# filterbank_amp.net
KiCad netlist of a schematic drawn in Altium Designer
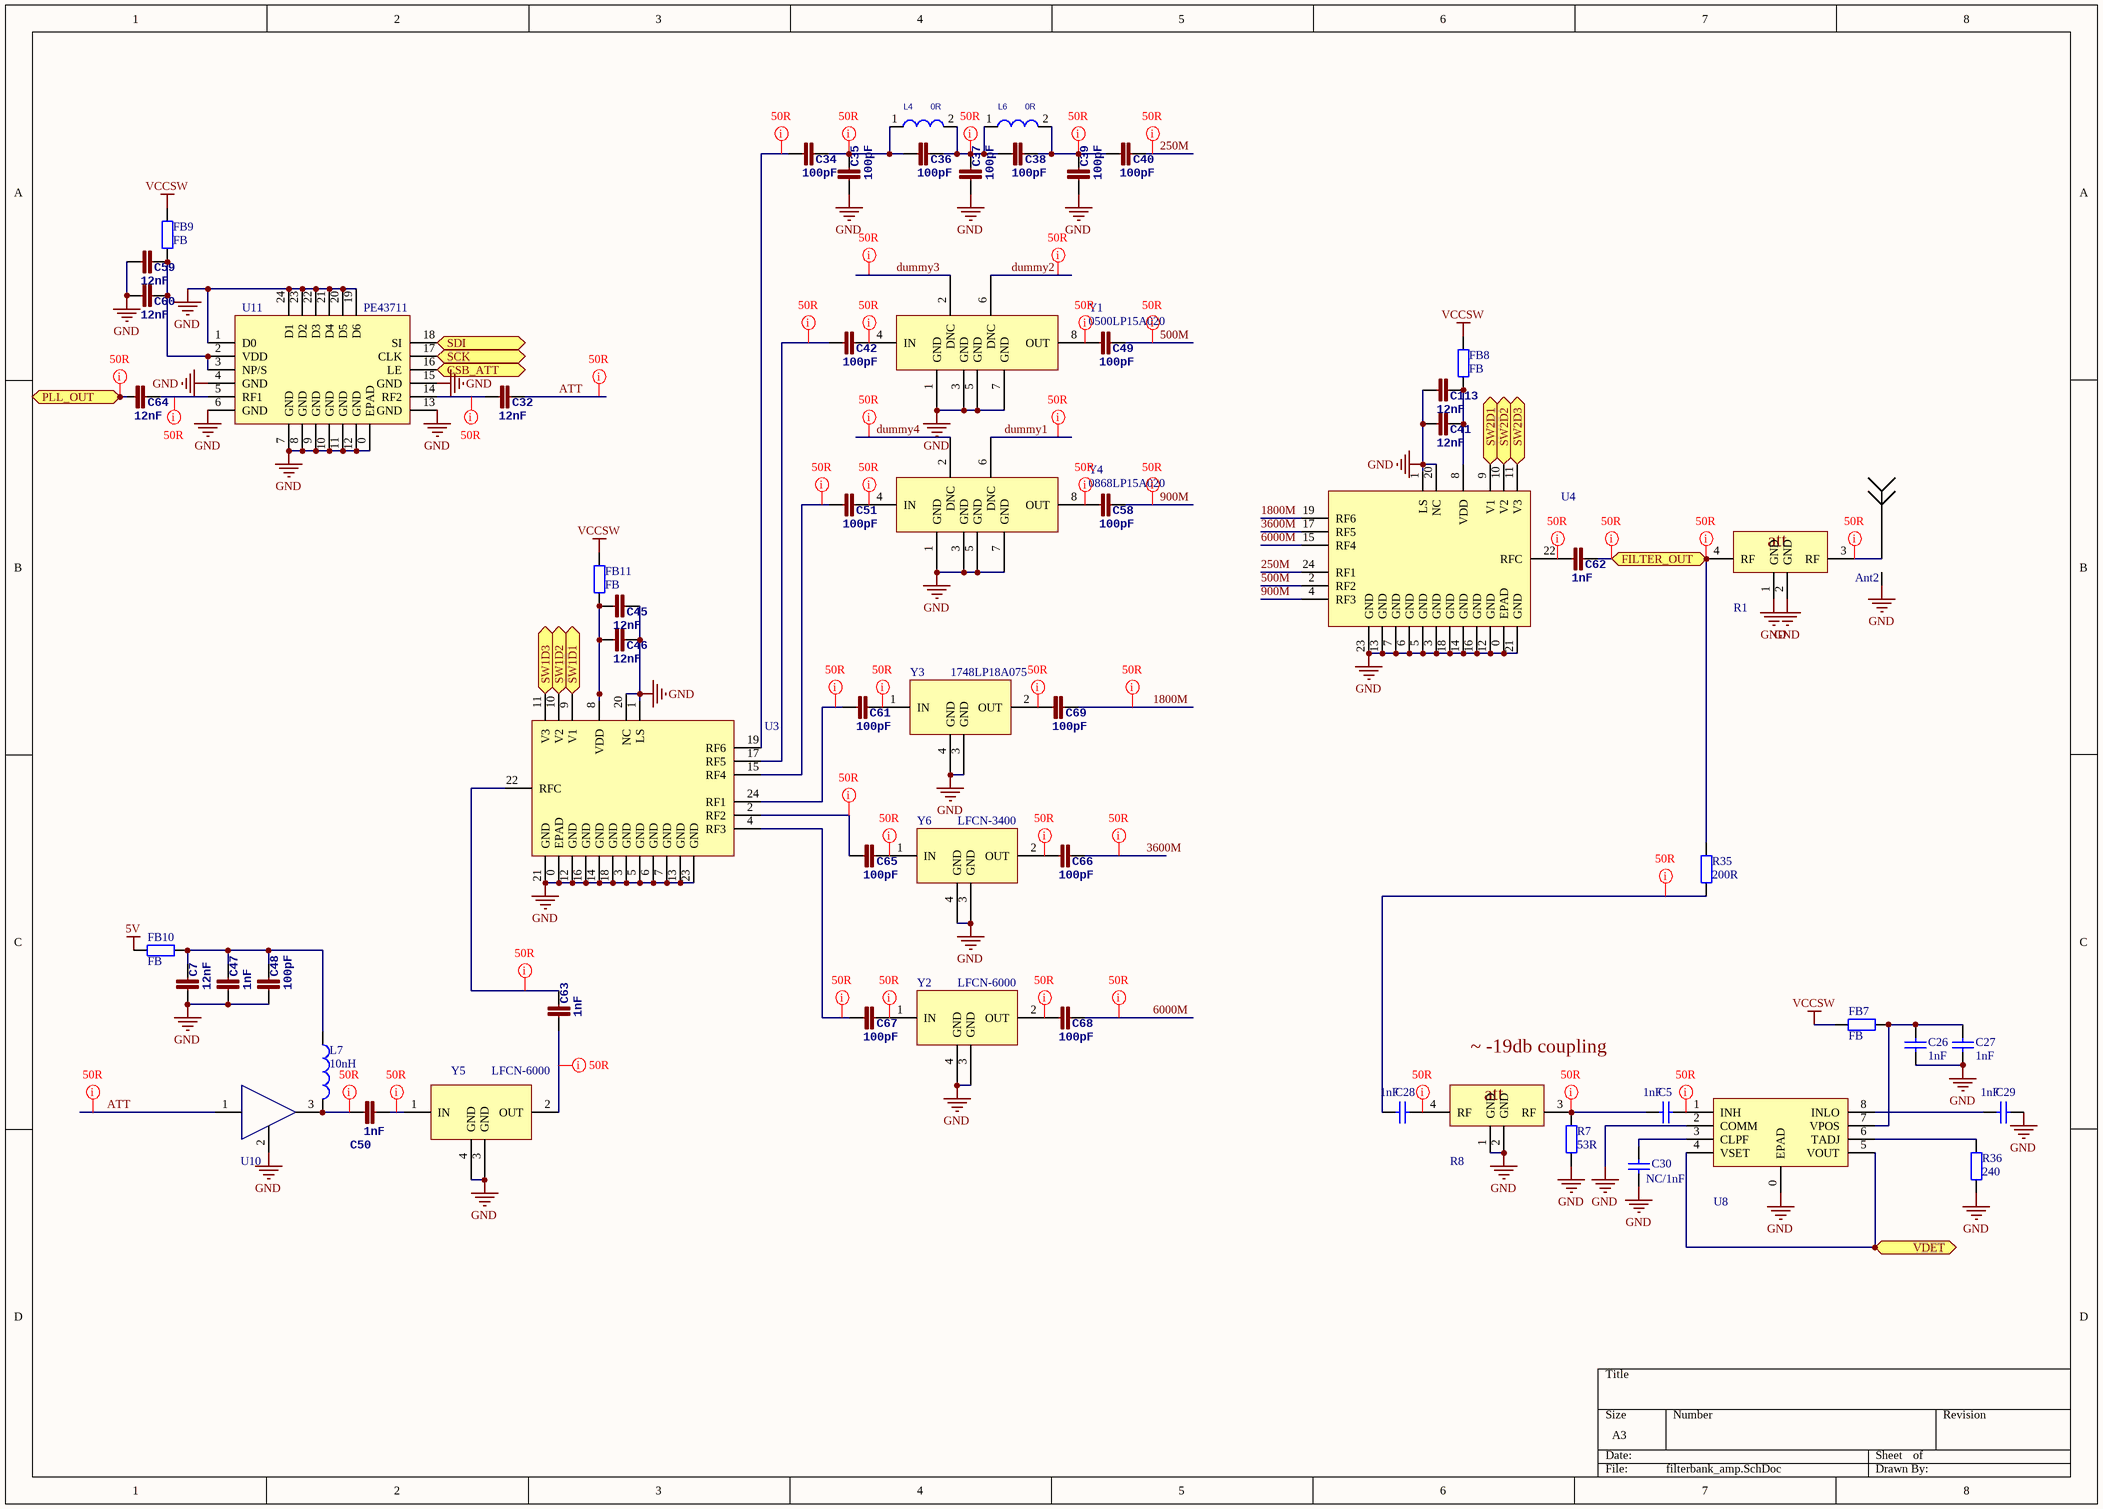
[diagram p0: filterbank_amp.SchDoc]

(export (version "E")
  (design (tool "Eeschema 10.0.6"))
  (components
    (comp (ref "Ant2") (value "Antenna") (footprint "SMA-2") (libsource (lib "F4SDR") (part "Antenna")))
    (comp (ref "C5")
      (value "1nF")
      (footprint "0402")
      (description "Capacitor")
      (fields (field (name "PUBLISHER") "Altium Limited"))
      (libsource (lib "RTC6705") (part "Cap"))
    )
    (comp (ref "C7")
      (value "12nF")
      (footprint "0805")
      (description "<b>Capacitor</b>\nStandard 0603 ceramic capacitor, and 0.1\" leaded capacitor.")
      (fields (field (name "PARTNO") "CC0402ZRY5V7BB104"))
      (libsource (lib "pixhawk2") (part "CAP0402-CAP"))
    )
    (comp (ref "C26")
      (value "1nF")
      (footprint "0402")
      (description "Capacitor")
      (fields (field (name "PUBLISHER") "Altium Limited"))
      (libsource (lib "RTC6705") (part "Cap"))
    )
    (comp (ref "C27")
      (value "1nF")
      (footprint "0402")
      (description "Capacitor")
      (fields (field (name "PUBLISHER") "Altium Limited"))
      (libsource (lib "RTC6705") (part "Cap"))
    )
    (comp (ref "C28")
      (value "1nF")
      (footprint "0402")
      (description "Capacitor")
      (fields (field (name "PUBLISHER") "Altium Limited"))
      (libsource (lib "RTC6705") (part "Cap"))
    )
    (comp (ref "C29")
      (value "1nF")
      (footprint "0402")
      (description "Capacitor")
      (fields (field (name "PUBLISHER") "Altium Limited"))
      (libsource (lib "RTC6705") (part "Cap"))
    )
    (comp (ref "C30")
      (value "NC/1nF")
      (footprint "0402")
      (description "Capacitor")
      (fields (field (name "PUBLISHER") "Altium Limited"))
      (libsource (lib "RTC6705") (part "Cap"))
    )
    (comp (ref "C32")
      (value "12nF")
      (footprint "0402")
      (description "<b>Capacitor</b>\nStandard 0603 ceramic capacitor, and 0.1\" leaded capacitor.")
      (fields (field (name "PARTNO") "CC0402ZRY5V7BB104"))
      (libsource (lib "") (part "CAP0402-CAP_1"))
    )
    (comp (ref "C34")
      (value "100pF")
      (footprint "0402")
      (description "<b>Capacitor</b>\nStandard 0603 ceramic capacitor, and 0.1\" leaded capacitor.")
      (fields (field (name "PARTNO") "CC0402ZRY5V7BB104"))
      (libsource (lib "") (part "CAP0402-CAP_1"))
    )
    (comp (ref "C35")
      (value "100pF")
      (footprint "0402")
      (description "<b>Capacitor</b>\nStandard 0603 ceramic capacitor, and 0.1\" leaded capacitor.")
      (fields (field (name "PARTNO") "CC0402ZRY5V7BB104"))
      (libsource (lib "pixhawk2") (part "CAP0402-CAP"))
    )
    (comp (ref "C36")
      (value "100pF")
      (footprint "0402")
      (description "<b>Capacitor</b>\nStandard 0603 ceramic capacitor, and 0.1\" leaded capacitor.")
      (fields (field (name "PARTNO") "CC0402ZRY5V7BB104"))
      (libsource (lib "") (part "CAP0402-CAP_1"))
    )
    (comp (ref "C37")
      (value "100pF")
      (footprint "0402")
      (description "<b>Capacitor</b>\nStandard 0603 ceramic capacitor, and 0.1\" leaded capacitor.")
      (fields (field (name "PARTNO") "CC0402ZRY5V7BB104"))
      (libsource (lib "pixhawk2") (part "CAP0402-CAP"))
    )
    (comp (ref "C38")
      (value "100pF")
      (footprint "0402")
      (description "<b>Capacitor</b>\nStandard 0603 ceramic capacitor, and 0.1\" leaded capacitor.")
      (fields (field (name "PARTNO") "CC0402ZRY5V7BB104"))
      (libsource (lib "") (part "CAP0402-CAP_1"))
    )
    (comp (ref "C39")
      (value "100pF")
      (footprint "0402")
      (description "<b>Capacitor</b>\nStandard 0603 ceramic capacitor, and 0.1\" leaded capacitor.")
      (fields (field (name "PARTNO") "CC0402ZRY5V7BB104"))
      (libsource (lib "pixhawk2") (part "CAP0402-CAP"))
    )
    (comp (ref "C40")
      (value "100pF")
      (footprint "0402")
      (description "<b>Capacitor</b>\nStandard 0603 ceramic capacitor, and 0.1\" leaded capacitor.")
      (fields (field (name "PARTNO") "CC0402ZRY5V7BB104"))
      (libsource (lib "") (part "CAP0402-CAP_1"))
    )
    (comp (ref "C41")
      (value "12nF")
      (footprint "0402")
      (description "<b>Capacitor</b>\nStandard 0603 ceramic capacitor, and 0.1\" leaded capacitor.")
      (fields (field (name "PARTNO") "CC0402ZRY5V7BB104"))
      (libsource (lib "") (part "CAP0402-CAP_1"))
    )
    (comp (ref "C42")
      (value "100pF")
      (footprint "0402")
      (description "<b>Capacitor</b>\nStandard 0603 ceramic capacitor, and 0.1\" leaded capacitor.")
      (fields (field (name "PARTNO") "CC0402ZRY5V7BB104"))
      (libsource (lib "") (part "CAP0402-CAP_1"))
    )
    (comp (ref "C45")
      (value "12nF")
      (footprint "0402")
      (description "<b>Capacitor</b>\nStandard 0603 ceramic capacitor, and 0.1\" leaded capacitor.")
      (fields (field (name "PARTNO") "CC0402ZRY5V7BB104"))
      (libsource (lib "") (part "CAP0402-CAP_1"))
    )
    (comp (ref "C46")
      (value "12nF")
      (footprint "0402")
      (description "<b>Capacitor</b>\nStandard 0603 ceramic capacitor, and 0.1\" leaded capacitor.")
      (fields (field (name "PARTNO") "CC0402ZRY5V7BB104"))
      (libsource (lib "") (part "CAP0402-CAP_1"))
    )
    (comp (ref "C47")
      (value "1nF")
      (footprint "0402")
      (description "<b>Capacitor</b>\nStandard 0603 ceramic capacitor, and 0.1\" leaded capacitor.")
      (fields (field (name "PARTNO") "CC0402ZRY5V7BB104"))
      (libsource (lib "pixhawk2") (part "CAP0402-CAP"))
    )
    (comp (ref "C48")
      (value "100pF")
      (footprint "0402")
      (description "<b>Capacitor</b>\nStandard 0603 ceramic capacitor, and 0.1\" leaded capacitor.")
      (fields (field (name "PARTNO") "CC0402ZRY5V7BB104"))
      (libsource (lib "pixhawk2") (part "CAP0402-CAP"))
    )
    (comp (ref "C49")
      (value "100pF")
      (footprint "0402")
      (description "<b>Capacitor</b>\nStandard 0603 ceramic capacitor, and 0.1\" leaded capacitor.")
      (fields (field (name "PARTNO") "CC0402ZRY5V7BB104"))
      (libsource (lib "") (part "CAP0402-CAP_1"))
    )
    (comp (ref "C50")
      (value "1nF")
      (footprint "0402")
      (description "<b>Capacitor</b>\nStandard 0603 ceramic capacitor, and 0.1\" leaded capacitor.")
      (fields (field (name "PARTNO") "CC0402ZRY5V7BB104"))
      (libsource (lib "") (part "CAP0402-CAP_1"))
    )
    (comp (ref "C51")
      (value "100pF")
      (footprint "0402")
      (description "<b>Capacitor</b>\nStandard 0603 ceramic capacitor, and 0.1\" leaded capacitor.")
      (fields (field (name "PARTNO") "CC0402ZRY5V7BB104"))
      (libsource (lib "") (part "CAP0402-CAP_1"))
    )
    (comp (ref "C58")
      (value "100pF")
      (footprint "0402")
      (description "<b>Capacitor</b>\nStandard 0603 ceramic capacitor, and 0.1\" leaded capacitor.")
      (fields (field (name "PARTNO") "CC0402ZRY5V7BB104"))
      (libsource (lib "") (part "CAP0402-CAP_1"))
    )
    (comp (ref "C59")
      (value "12nF")
      (footprint "0402")
      (description "<b>Capacitor</b>\nStandard 0603 ceramic capacitor, and 0.1\" leaded capacitor.")
      (fields (field (name "PARTNO") "CC0402ZRY5V7BB104"))
      (libsource (lib "") (part "CAP0402-CAP_1"))
    )
    (comp (ref "C60")
      (value "12nF")
      (footprint "0402")
      (description "<b>Capacitor</b>\nStandard 0603 ceramic capacitor, and 0.1\" leaded capacitor.")
      (fields (field (name "PARTNO") "CC0402ZRY5V7BB104"))
      (libsource (lib "") (part "CAP0402-CAP_1"))
    )
    (comp (ref "C61")
      (value "100pF")
      (footprint "0402")
      (description "<b>Capacitor</b>\nStandard 0603 ceramic capacitor, and 0.1\" leaded capacitor.")
      (fields (field (name "PARTNO") "CC0402ZRY5V7BB104"))
      (libsource (lib "") (part "CAP0402-CAP_1"))
    )
    (comp (ref "C62")
      (value "1nF")
      (footprint "0402")
      (description "<b>Capacitor</b>\nStandard 0603 ceramic capacitor, and 0.1\" leaded capacitor.")
      (fields (field (name "PARTNO") "CC0402ZRY5V7BB104"))
      (libsource (lib "") (part "CAP0402-CAP_1"))
    )
    (comp (ref "C63")
      (value "1nF")
      (footprint "0402")
      (description "<b>Capacitor</b>\nStandard 0603 ceramic capacitor, and 0.1\" leaded capacitor.")
      (fields (field (name "PARTNO") "CC0402ZRY5V7BB104"))
      (libsource (lib "pixhawk2") (part "CAP0402-CAP"))
    )
    (comp (ref "C64")
      (value "12nF")
      (footprint "0402")
      (description "<b>Capacitor</b>\nStandard 0603 ceramic capacitor, and 0.1\" leaded capacitor.")
      (fields (field (name "PARTNO") "CC0402ZRY5V7BB104"))
      (libsource (lib "") (part "CAP0402-CAP_1"))
    )
    (comp (ref "C65")
      (value "100pF")
      (footprint "0402")
      (description "<b>Capacitor</b>\nStandard 0603 ceramic capacitor, and 0.1\" leaded capacitor.")
      (fields (field (name "PARTNO") "CC0402ZRY5V7BB104"))
      (libsource (lib "") (part "CAP0402-CAP_1"))
    )
    (comp (ref "C66")
      (value "100pF")
      (footprint "0402")
      (description "<b>Capacitor</b>\nStandard 0603 ceramic capacitor, and 0.1\" leaded capacitor.")
      (fields (field (name "PARTNO") "CC0402ZRY5V7BB104"))
      (libsource (lib "") (part "CAP0402-CAP_1"))
    )
    (comp (ref "C67")
      (value "100pF")
      (footprint "0402")
      (description "<b>Capacitor</b>\nStandard 0603 ceramic capacitor, and 0.1\" leaded capacitor.")
      (fields (field (name "PARTNO") "CC0402ZRY5V7BB104"))
      (libsource (lib "") (part "CAP0402-CAP_1"))
    )
    (comp (ref "C68")
      (value "100pF")
      (footprint "0402")
      (description "<b>Capacitor</b>\nStandard 0603 ceramic capacitor, and 0.1\" leaded capacitor.")
      (fields (field (name "PARTNO") "CC0402ZRY5V7BB104"))
      (libsource (lib "") (part "CAP0402-CAP_1"))
    )
    (comp (ref "C69")
      (value "100pF")
      (footprint "0402")
      (description "<b>Capacitor</b>\nStandard 0603 ceramic capacitor, and 0.1\" leaded capacitor.")
      (fields (field (name "PARTNO") "CC0402ZRY5V7BB104"))
      (libsource (lib "") (part "CAP0402-CAP_1"))
    )
    (comp (ref "C113")
      (value "12nF")
      (footprint "0402")
      (description "<b>Capacitor</b>\nStandard 0603 ceramic capacitor, and 0.1\" leaded capacitor.")
      (fields (field (name "PARTNO") "CC0402ZRY5V7BB104"))
      (libsource (lib "") (part "CAP0402-CAP_1"))
    )
    (comp (ref "FB7")
      (value "FB")
      (footprint "0402")
      (description "Resistor")
      (fields (field (name "PUBLISHER") "Altium Limited"))
      (libsource (lib "Miscellaneous Devices") (part "Res2"))
    )
    (comp (ref "FB8")
      (value "FB")
      (footprint "0402")
      (description "Resistor")
      (fields (field (name "PUBLISHER") "Altium Limited"))
      (libsource (lib "") (part "Res2_1"))
    )
    (comp (ref "FB9")
      (value "FB")
      (footprint "0402")
      (description "Resistor")
      (fields (field (name "PUBLISHER") "Altium Limited"))
      (libsource (lib "") (part "Res2_1"))
    )
    (comp (ref "FB10")
      (value "FB")
      (footprint "0402")
      (description "Resistor")
      (fields (field (name "PUBLISHER") "Altium Limited"))
      (libsource (lib "Miscellaneous Devices") (part "Res2"))
    )
    (comp (ref "FB11")
      (value "FB")
      (footprint "0402")
      (description "Resistor")
      (fields (field (name "PUBLISHER") "Altium Limited"))
      (libsource (lib "") (part "Res2_1"))
    )
    (comp (ref "L4") (value "0R") (footprint "0402") (libsource (lib "*") (part "L/2.5*2.0")))
    (comp (ref "L6") (value "0R") (footprint "0402") (libsource (lib "*") (part "L/2.5*2.0")))
    (comp (ref "L7")
      (value "10nH")
      (footprint "0402")
      (description "Inductor")
      (fields (field (name "PUBLISHER") "Altium Limited"))
      (libsource (lib "Miscellaneous Devices") (part "Inductor"))
    )
    (comp (ref "R1")
      (value "EXB24-RF-ATT")
      (footprint "EXB24AT-RF-ATT")
      (libsource (lib "F4SDR") (part "EXB24-RF-ATT"))
    )
    (comp (ref "R7")
      (value "53R")
      (footprint "0402")
      (description "Resistor")
      (fields (field (name "PUBLISHER") "Altium Limited"))
      (libsource (lib "") (part "Res2_2"))
    )
    (comp (ref "R8")
      (value "EXB24-RF-ATT")
      (footprint "EXB24AT-RF-ATT")
      (libsource (lib "F4SDR") (part "EXB24-RF-ATT"))
    )
    (comp (ref "R35")
      (value "200R")
      (footprint "0402")
      (description "Resistor")
      (fields (field (name "PUBLISHER") "Altium Limited"))
      (libsource (lib "") (part "Res2_2"))
    )
    (comp (ref "R36")
      (value "240")
      (footprint "0402")
      (description "Resistor")
      (fields (field (name "PUBLISHER") "Altium Limited"))
      (libsource (lib "") (part "Res2_2"))
    )
    (comp (ref "U3") (value "PE42462") (footprint "PE42462") (libsource (lib "F4SDR") (part "PE42462")))
    (comp (ref "U4") (value "PE42462") (footprint "PE42462") (libsource (lib "") (part "PE42462_1")))
    (comp (ref "U8") (value "AD8319") (footprint "AD8319") (libsource (lib "F4SDR") (part "AD8319")))
    (comp (ref "U10") (value "AMP-SOT89") (footprint "SOT-89") (libsource (lib "F4SDR") (part "AMP-SOT89")))
    (comp (ref "U11") (value "PE43711") (footprint "PE43711") (libsource (lib "F4SDR") (part "PE43711")))
    (comp (ref "Y1")
      (value "0500LP15A020")
      (footprint "5515LP15A730/0868LP15A020")
      (libsource (lib "F4SDR") (part "5515LP15A730/0868LP15A020"))
    )
    (comp (ref "Y2")
      (value "LFCN-6000")
      (footprint "1748LP18A075")
      (libsource (lib "F4SDR") (part "1748LP18A075"))
    )
    (comp (ref "Y3")
      (value "1748LP18A075")
      (footprint "1748LP18A075")
      (libsource (lib "F4SDR") (part "1748LP18A075"))
    )
    (comp (ref "Y4")
      (value "0868LP15A020")
      (footprint "5515LP15A730/0868LP15A020")
      (libsource (lib "F4SDR") (part "5515LP15A730/0868LP15A020"))
    )
    (comp (ref "Y5")
      (value "LFCN-6000")
      (footprint "1748LP18A075")
      (libsource (lib "F4SDR") (part "1748LP18A075"))
    )
    (comp (ref "Y6")
      (value "LFCN-3400")
      (footprint "1748LP18A075")
      (libsource (lib "F4SDR") (part "1748LP18A075"))
    )
  )
  (nets
    (net (code "1") (name "/250M") (class "Default")
      (node (ref "C40") (pin "2") (pinfunction "2_2") (pintype "passive"))
      (node (ref "U4") (pin "24") (pinfunction "RF1_24") (pintype "passive"))
    )
    (net (code "2") (name "/500M") (class "Default")
      (node (ref "C49") (pin "2") (pinfunction "2_2") (pintype "passive"))
      (node (ref "U4") (pin "2") (pinfunction "RF2_2") (pintype "passive"))
    )
    (net (code "3") (name "/900M") (class "Default")
      (node (ref "C58") (pin "2") (pinfunction "2_2") (pintype "passive"))
      (node (ref "U4") (pin "4") (pinfunction "RF3_4") (pintype "passive"))
    )
    (net (code "4") (name "/1800M") (class "Default")
      (node (ref "C69") (pin "2") (pinfunction "2_2") (pintype "passive"))
      (node (ref "U4") (pin "19") (pinfunction "RF6_19") (pintype "passive"))
    )
    (net (code "5") (name "/3600M") (class "Default")
      (node (ref "C66") (pin "2") (pinfunction "2_2") (pintype "passive"))
      (node (ref "U4") (pin "17") (pinfunction "RF5_17") (pintype "passive"))
    )
    (net (code "6") (name "/6000M") (class "Default")
      (node (ref "C68") (pin "2") (pinfunction "2_2") (pintype "passive"))
      (node (ref "U4") (pin "15") (pinfunction "RF4_15") (pintype "passive"))
    )
    (net (code "7") (name "/ATT") (class "Default")
      (node (ref "C32") (pin "2") (pinfunction "2_2") (pintype "passive"))
      (node (ref "U10") (pin "1") (pinfunction "1_1") (pintype "passive"))
    )
    (net (code "8") (name "/CSB_ATT") (class "Default")
      (node (ref "U11") (pin "16") (pinfunction "LE_16") (pintype "passive"))
    )
    (net (code "9") (name "/FILTER_OUT") (class "Default")
      (node (ref "C62") (pin "2") (pinfunction "2_2") (pintype "passive"))
      (node (ref "R1") (pin "4") (pinfunction "RF_4") (pintype "passive"))
      (node (ref "R35") (pin "1") (pinfunction "1_1") (pintype "passive"))
    )
    (net (code "10") (name "/PLL_OUT") (class "Default")
      (node (ref "C64") (pin "1") (pinfunction "1_1") (pintype "passive"))
    )
    (net (code "11") (name "/SCK") (class "Default")
      (node (ref "U11") (pin "17") (pinfunction "CLK_17") (pintype "passive"))
    )
    (net (code "12") (name "/SDI") (class "Default")
      (node (ref "U11") (pin "18") (pinfunction "SI_18") (pintype "passive"))
    )
    (net (code "13") (name "/SW1D1") (class "Default")
      (node (ref "U3") (pin "9") (pinfunction "V1_9") (pintype "passive"))
    )
    (net (code "14") (name "/SW1D2") (class "Default")
      (node (ref "U3") (pin "10") (pinfunction "V2_10") (pintype "passive"))
    )
    (net (code "15") (name "/SW1D3") (class "Default")
      (node (ref "U3") (pin "11") (pinfunction "V3_11") (pintype "passive"))
    )
    (net (code "16") (name "/SW2D1") (class "Default")
      (node (ref "U4") (pin "9") (pinfunction "V1_9") (pintype "passive"))
    )
    (net (code "17") (name "/SW2D2") (class "Default")
      (node (ref "U4") (pin "10") (pinfunction "V2_10") (pintype "passive"))
    )
    (net (code "18") (name "/SW2D3") (class "Default")
      (node (ref "U4") (pin "11") (pinfunction "V3_11") (pintype "passive"))
    )
    (net (code "19") (name "/VDET") (class "Default")
      (node (ref "U8") (pin "4") (pinfunction "VSET_4") (pintype "passive"))
      (node (ref "U8") (pin "5") (pinfunction "VOUT_5") (pintype "passive"))
    )
    (net (code "20") (name "/dummy1") (class "Default")
      (node (ref "Y4") (pin "6") (pinfunction "DNC_6") (pintype "passive"))
    )
    (net (code "21") (name "/dummy2") (class "Default")
      (node (ref "Y1") (pin "6") (pinfunction "DNC_6") (pintype "passive"))
    )
    (net (code "22") (name "/dummy3") (class "Default")
      (node (ref "Y1") (pin "2") (pinfunction "DNC_2") (pintype "passive"))
    )
    (net (code "23") (name "/dummy4") (class "Default")
      (node (ref "Y4") (pin "2") (pinfunction "DNC_2") (pintype "passive"))
    )
    (net (code "24") (name "5V") (class "Default")
      (node (ref "FB10") (pin "1") (pinfunction "1_1") (pintype "passive"))
    )
    (net (code "25") (name "GND") (class "Default")
      (node (ref "Ant2") (pin "GND") (pinfunction "G_GND") (pintype "passive"))
      (node (ref "C113") (pin "1") (pinfunction "1_1") (pintype "passive"))
      (node (ref "C26") (pin "1") (pinfunction "1_1") (pintype "passive"))
      (node (ref "C27") (pin "1") (pinfunction "1_1") (pintype "passive"))
      (node (ref "C29") (pin "2") (pinfunction "2_2") (pintype "passive"))
      (node (ref "C30") (pin "1") (pinfunction "1_1") (pintype "passive"))
      (node (ref "C35") (pin "1") (pinfunction "1_1") (pintype "passive"))
      (node (ref "C37") (pin "1") (pinfunction "1_1") (pintype "passive"))
      (node (ref "C39") (pin "1") (pinfunction "1_1") (pintype "passive"))
      (node (ref "C41") (pin "1") (pinfunction "1_1") (pintype "passive"))
      (node (ref "C45") (pin "2") (pinfunction "2_2") (pintype "passive"))
      (node (ref "C46") (pin "2") (pinfunction "2_2") (pintype "passive"))
      (node (ref "C47") (pin "1") (pinfunction "1_1") (pintype "passive"))
      (node (ref "C48") (pin "1") (pinfunction "1_1") (pintype "passive"))
      (node (ref "C59") (pin "1") (pinfunction "1_1") (pintype "passive"))
      (node (ref "C60") (pin "1") (pinfunction "1_1") (pintype "passive"))
      (node (ref "C7") (pin "1") (pinfunction "1_1") (pintype "passive"))
      (node (ref "R1") (pin "1") (pinfunction "GND_1") (pintype "passive"))
      (node (ref "R1") (pin "2") (pinfunction "GND_2") (pintype "passive"))
      (node (ref "R36") (pin "2") (pinfunction "2_2") (pintype "passive"))
      (node (ref "R7") (pin "2") (pinfunction "2_2") (pintype "passive"))
      (node (ref "R8") (pin "1") (pinfunction "GND_1") (pintype "passive"))
      (node (ref "R8") (pin "2") (pinfunction "GND_2") (pintype "passive"))
      (node (ref "U10") (pin "2") (pinfunction "2_2") (pintype "passive"))
      (node (ref "U11") (pin "0") (pinfunction "EPAD_0") (pintype "passive"))
      (node (ref "U11") (pin "1") (pinfunction "D0_1") (pintype "passive"))
      (node (ref "U11") (pin "10") (pinfunction "GND_10") (pintype "passive"))
      (node (ref "U11") (pin "11") (pinfunction "GND_11") (pintype "passive"))
      (node (ref "U11") (pin "12") (pinfunction "GND_12") (pintype "passive"))
      (node (ref "U11") (pin "13") (pinfunction "GND_13") (pintype "passive"))
      (node (ref "U11") (pin "15") (pinfunction "GND_15") (pintype "passive"))
      (node (ref "U11") (pin "19") (pinfunction "D6_19") (pintype "passive"))
      (node (ref "U11") (pin "20") (pinfunction "D5_20") (pintype "passive"))
      (node (ref "U11") (pin "21") (pinfunction "D4_21") (pintype "passive"))
      (node (ref "U11") (pin "22") (pinfunction "D3_22") (pintype "passive"))
      (node (ref "U11") (pin "23") (pinfunction "D2_23") (pintype "passive"))
      (node (ref "U11") (pin "24") (pinfunction "D1_24") (pintype "passive"))
      (node (ref "U11") (pin "4") (pinfunction "GND_4") (pintype "passive"))
      (node (ref "U11") (pin "6") (pinfunction "GND_6") (pintype "passive"))
      (node (ref "U11") (pin "7") (pinfunction "GND_7") (pintype "passive"))
      (node (ref "U11") (pin "8") (pinfunction "GND_8") (pintype "passive"))
      (node (ref "U11") (pin "9") (pinfunction "GND_9") (pintype "passive"))
      (node (ref "U3") (pin "0") (pinfunction "EPAD_0") (pintype "passive"))
      (node (ref "U3") (pin "1") (pinfunction "LS_1") (pintype "passive"))
      (node (ref "U3") (pin "12") (pinfunction "GND_12") (pintype "passive"))
      (node (ref "U3") (pin "13") (pinfunction "GND_13") (pintype "passive"))
      (node (ref "U3") (pin "14") (pinfunction "GND_14") (pintype "passive"))
      (node (ref "U3") (pin "16") (pinfunction "GND_16") (pintype "passive"))
      (node (ref "U3") (pin "18") (pinfunction "GND_18") (pintype "passive"))
      (node (ref "U3") (pin "20") (pinfunction "NC_20") (pintype "passive"))
      (node (ref "U3") (pin "21") (pinfunction "GND_21") (pintype "passive"))
      (node (ref "U3") (pin "23") (pinfunction "GND_23") (pintype "passive"))
      (node (ref "U3") (pin "3") (pinfunction "GND_3") (pintype "passive"))
      (node (ref "U3") (pin "5") (pinfunction "GND_5") (pintype "passive"))
      (node (ref "U3") (pin "6") (pinfunction "GND_6") (pintype "passive"))
      (node (ref "U3") (pin "7") (pinfunction "GND_7") (pintype "passive"))
      (node (ref "U4") (pin "0") (pinfunction "EPAD_0") (pintype "passive"))
      (node (ref "U4") (pin "1") (pinfunction "LS_1") (pintype "passive"))
      (node (ref "U4") (pin "12") (pinfunction "GND_12") (pintype "passive"))
      (node (ref "U4") (pin "13") (pinfunction "GND_13") (pintype "passive"))
      (node (ref "U4") (pin "14") (pinfunction "GND_14") (pintype "passive"))
      (node (ref "U4") (pin "16") (pinfunction "GND_16") (pintype "passive"))
      (node (ref "U4") (pin "18") (pinfunction "GND_18") (pintype "passive"))
      (node (ref "U4") (pin "20") (pinfunction "NC_20") (pintype "passive"))
      (node (ref "U4") (pin "21") (pinfunction "GND_21") (pintype "passive"))
      (node (ref "U4") (pin "23") (pinfunction "GND_23") (pintype "passive"))
      (node (ref "U4") (pin "3") (pinfunction "GND_3") (pintype "passive"))
      (node (ref "U4") (pin "5") (pinfunction "GND_5") (pintype "passive"))
      (node (ref "U4") (pin "6") (pinfunction "GND_6") (pintype "passive"))
      (node (ref "U4") (pin "7") (pinfunction "GND_7") (pintype "passive"))
      (node (ref "U8") (pin "0") (pinfunction "EPAD_0") (pintype "passive"))
      (node (ref "U8") (pin "2") (pinfunction "COMM_2") (pintype "passive"))
      (node (ref "Y1") (pin "1") (pinfunction "GND_1") (pintype "passive"))
      (node (ref "Y1") (pin "3") (pinfunction "GND_3") (pintype "passive"))
      (node (ref "Y1") (pin "5") (pinfunction "GND_5") (pintype "passive"))
      (node (ref "Y1") (pin "7") (pinfunction "GND_7") (pintype "passive"))
      (node (ref "Y2") (pin "3") (pinfunction "GND_3") (pintype "passive"))
      (node (ref "Y2") (pin "4") (pinfunction "GND_4") (pintype "passive"))
      (node (ref "Y3") (pin "3") (pinfunction "GND_3") (pintype "passive"))
      (node (ref "Y3") (pin "4") (pinfunction "GND_4") (pintype "passive"))
      (node (ref "Y4") (pin "1") (pinfunction "GND_1") (pintype "passive"))
      (node (ref "Y4") (pin "3") (pinfunction "GND_3") (pintype "passive"))
      (node (ref "Y4") (pin "5") (pinfunction "GND_5") (pintype "passive"))
      (node (ref "Y4") (pin "7") (pinfunction "GND_7") (pintype "passive"))
      (node (ref "Y5") (pin "3") (pinfunction "GND_3") (pintype "passive"))
      (node (ref "Y5") (pin "4") (pinfunction "GND_4") (pintype "passive"))
      (node (ref "Y6") (pin "3") (pinfunction "GND_3") (pintype "passive"))
      (node (ref "Y6") (pin "4") (pinfunction "GND_4") (pintype "passive"))
    )
    (net (code "26") (name "Net-(Ant2-Pad1)") (class "Default")
      (node (ref "Ant2") (pin "1") (pinfunction "1_1") (pintype "passive"))
      (node (ref "R1") (pin "3") (pinfunction "RF_3") (pintype "passive"))
    )
    (net (code "27") (name "Net-(C5-Pad1)") (class "Default")
      (node (ref "C5") (pin "1") (pinfunction "1_1") (pintype "passive"))
      (node (ref "R7") (pin "1") (pinfunction "1_1") (pintype "passive"))
      (node (ref "R8") (pin "3") (pinfunction "RF_3") (pintype "passive"))
    )
    (net (code "28") (name "Net-(C28-Pad1)") (class "Default")
      (node (ref "C28") (pin "1") (pinfunction "1_1") (pintype "passive"))
      (node (ref "R35") (pin "2") (pinfunction "2_2") (pintype "passive"))
    )
    (net (code "29") (name "Net-(C28-Pad2)") (class "Default")
      (node (ref "C28") (pin "2") (pinfunction "2_2") (pintype "passive"))
      (node (ref "R8") (pin "4") (pinfunction "RF_4") (pintype "passive"))
    )
    (net (code "30") (name "Net-(C34-Pad2)") (class "Default")
      (node (ref "C34") (pin "2") (pinfunction "2_2") (pintype "passive"))
      (node (ref "C35") (pin "2") (pinfunction "2_2") (pintype "passive"))
      (node (ref "C36") (pin "1") (pinfunction "1_1") (pintype "passive"))
      (node (ref "L4") (pin "1") (pinfunction "1_1") (pintype "passive"))
    )
    (net (code "31") (name "Net-(C36-Pad2)") (class "Default")
      (node (ref "C36") (pin "2") (pinfunction "2_2") (pintype "passive"))
      (node (ref "C37") (pin "2") (pinfunction "2_2") (pintype "passive"))
      (node (ref "C38") (pin "1") (pinfunction "1_1") (pintype "passive"))
      (node (ref "L4") (pin "2") (pinfunction "2_2") (pintype "passive"))
      (node (ref "L6") (pin "1") (pinfunction "1_1") (pintype "passive"))
    )
    (net (code "32") (name "Net-(C38-Pad2)") (class "Default")
      (node (ref "C38") (pin "2") (pinfunction "2_2") (pintype "passive"))
      (node (ref "C39") (pin "2") (pinfunction "2_2") (pintype "passive"))
      (node (ref "C40") (pin "1") (pinfunction "1_1") (pintype "passive"))
      (node (ref "L6") (pin "2") (pinfunction "2_2") (pintype "passive"))
    )
    (net (code "33") (name "Net-(C47-Pad2)") (class "Default")
      (node (ref "C47") (pin "2") (pinfunction "2_2") (pintype "passive"))
      (node (ref "C48") (pin "2") (pinfunction "2_2") (pintype "passive"))
      (node (ref "C7") (pin "2") (pinfunction "2_2") (pintype "passive"))
      (node (ref "FB10") (pin "2") (pinfunction "2_2") (pintype "passive"))
      (node (ref "L7") (pin "1") (pinfunction "1_1") (pintype "passive"))
    )
    (net (code "34") (name "Net-(C50-Pad1)") (class "Default")
      (node (ref "C50") (pin "1") (pinfunction "1_1") (pintype "passive"))
      (node (ref "L7") (pin "2") (pinfunction "2_2") (pintype "passive"))
      (node (ref "U10") (pin "3") (pinfunction "3_3") (pintype "passive"))
    )
    (net (code "35") (name "Net-(U3-RF1)") (class "Default")
      (node (ref "C61") (pin "1") (pinfunction "1_1") (pintype "passive"))
      (node (ref "U3") (pin "24") (pinfunction "RF1_24") (pintype "passive"))
    )
    (net (code "36") (name "Net-(U3-RF2)") (class "Default")
      (node (ref "C65") (pin "1") (pinfunction "1_1") (pintype "passive"))
      (node (ref "U3") (pin "2") (pinfunction "RF2_2") (pintype "passive"))
    )
    (net (code "37") (name "Net-(U3-RF3)") (class "Default")
      (node (ref "C67") (pin "1") (pinfunction "1_1") (pintype "passive"))
      (node (ref "U3") (pin "4") (pinfunction "RF3_4") (pintype "passive"))
    )
    (net (code "38") (name "Net-(U3-RF4)") (class "Default")
      (node (ref "C51") (pin "1") (pinfunction "1_1") (pintype "passive"))
      (node (ref "U3") (pin "15") (pinfunction "RF4_15") (pintype "passive"))
    )
    (net (code "39") (name "Net-(U3-RF5)") (class "Default")
      (node (ref "C42") (pin "1") (pinfunction "1_1") (pintype "passive"))
      (node (ref "U3") (pin "17") (pinfunction "RF5_17") (pintype "passive"))
    )
    (net (code "40") (name "Net-(U3-RF6)") (class "Default")
      (node (ref "C34") (pin "1") (pinfunction "1_1") (pintype "passive"))
      (node (ref "U3") (pin "19") (pinfunction "RF6_19") (pintype "passive"))
    )
    (net (code "41") (name "Net-(U3-RFC)") (class "Default")
      (node (ref "C63") (pin "2") (pinfunction "2_2") (pintype "passive"))
      (node (ref "U3") (pin "22") (pinfunction "RFC_22") (pintype "passive"))
    )
    (net (code "42") (name "Net-(U3-VDD)") (class "Default")
      (node (ref "C45") (pin "1") (pinfunction "1_1") (pintype "passive"))
      (node (ref "C46") (pin "1") (pinfunction "1_1") (pintype "passive"))
      (node (ref "FB11") (pin "1") (pinfunction "1_1") (pintype "passive"))
      (node (ref "U3") (pin "8") (pinfunction "VDD_8") (pintype "passive"))
    )
    (net (code "43") (name "Net-(U4-RFC)") (class "Default")
      (node (ref "C62") (pin "1") (pinfunction "1_1") (pintype "passive"))
      (node (ref "U4") (pin "22") (pinfunction "RFC_22") (pintype "passive"))
    )
    (net (code "44") (name "Net-(U4-VDD)") (class "Default")
      (node (ref "C113") (pin "2") (pinfunction "2_2") (pintype "passive"))
      (node (ref "C41") (pin "2") (pinfunction "2_2") (pintype "passive"))
      (node (ref "FB8") (pin "1") (pinfunction "1_1") (pintype "passive"))
      (node (ref "U4") (pin "8") (pinfunction "VDD_8") (pintype "passive"))
    )
    (net (code "45") (name "Net-(U8-CLPF)") (class "Default")
      (node (ref "C30") (pin "2") (pinfunction "2_2") (pintype "passive"))
      (node (ref "U8") (pin "3") (pinfunction "CLPF_3") (pintype "passive"))
    )
    (net (code "46") (name "Net-(U8-INH)") (class "Default")
      (node (ref "C5") (pin "2") (pinfunction "2_2") (pintype "passive"))
      (node (ref "U8") (pin "1") (pinfunction "INH_1") (pintype "passive"))
    )
    (net (code "47") (name "Net-(U8-INLO)") (class "Default")
      (node (ref "C29") (pin "1") (pinfunction "1_1") (pintype "passive"))
      (node (ref "U8") (pin "8") (pinfunction "INLO_8") (pintype "passive"))
    )
    (net (code "48") (name "Net-(U8-TADJ)") (class "Default")
      (node (ref "R36") (pin "1") (pinfunction "1_1") (pintype "passive"))
      (node (ref "U8") (pin "6") (pinfunction "TADJ_6") (pintype "passive"))
    )
    (net (code "49") (name "Net-(U8-VPOS)") (class "Default")
      (node (ref "C26") (pin "2") (pinfunction "2_2") (pintype "passive"))
      (node (ref "C27") (pin "2") (pinfunction "2_2") (pintype "passive"))
      (node (ref "FB7") (pin "2") (pinfunction "2_2") (pintype "passive"))
      (node (ref "U8") (pin "7") (pinfunction "VPOS_7") (pintype "passive"))
    )
    (net (code "50") (name "Net-(U11-NP{slash}S)") (class "Default")
      (node (ref "C59") (pin "2") (pinfunction "2_2") (pintype "passive"))
      (node (ref "C60") (pin "2") (pinfunction "2_2") (pintype "passive"))
      (node (ref "FB9") (pin "1") (pinfunction "1_1") (pintype "passive"))
      (node (ref "U11") (pin "2") (pinfunction "VDD_2") (pintype "passive"))
      (node (ref "U11") (pin "3") (pinfunction "NP/S_3") (pintype "passive"))
    )
    (net (code "51") (name "Net-(U11-RF1)") (class "Default")
      (node (ref "C64") (pin "2") (pinfunction "2_2") (pintype "passive"))
      (node (ref "U11") (pin "5") (pinfunction "RF1_5") (pintype "passive"))
    )
    (net (code "52") (name "Net-(U11-RF2)") (class "Default")
      (node (ref "C32") (pin "1") (pinfunction "1_1") (pintype "passive"))
      (node (ref "U11") (pin "14") (pinfunction "RF2_14") (pintype "passive"))
    )
    (net (code "53") (name "Net-(Y1-IN)") (class "Default")
      (node (ref "C42") (pin "2") (pinfunction "2_2") (pintype "passive"))
      (node (ref "Y1") (pin "4") (pinfunction "IN_4") (pintype "passive"))
    )
    (net (code "54") (name "Net-(Y1-OUT)") (class "Default")
      (node (ref "C49") (pin "1") (pinfunction "1_1") (pintype "passive"))
      (node (ref "Y1") (pin "8") (pinfunction "OUT_8") (pintype "passive"))
    )
    (net (code "55") (name "Net-(Y2-IN)") (class "Default")
      (node (ref "C67") (pin "2") (pinfunction "2_2") (pintype "passive"))
      (node (ref "Y2") (pin "1") (pinfunction "IN_1") (pintype "passive"))
    )
    (net (code "56") (name "Net-(Y2-OUT)") (class "Default")
      (node (ref "C68") (pin "1") (pinfunction "1_1") (pintype "passive"))
      (node (ref "Y2") (pin "2") (pinfunction "OUT_2") (pintype "passive"))
    )
    (net (code "57") (name "Net-(Y3-IN)") (class "Default")
      (node (ref "C61") (pin "2") (pinfunction "2_2") (pintype "passive"))
      (node (ref "Y3") (pin "1") (pinfunction "IN_1") (pintype "passive"))
    )
    (net (code "58") (name "Net-(Y3-OUT)") (class "Default")
      (node (ref "C69") (pin "1") (pinfunction "1_1") (pintype "passive"))
      (node (ref "Y3") (pin "2") (pinfunction "OUT_2") (pintype "passive"))
    )
    (net (code "59") (name "Net-(Y4-IN)") (class "Default")
      (node (ref "C51") (pin "2") (pinfunction "2_2") (pintype "passive"))
      (node (ref "Y4") (pin "4") (pinfunction "IN_4") (pintype "passive"))
    )
    (net (code "60") (name "Net-(Y4-OUT)") (class "Default")
      (node (ref "C58") (pin "1") (pinfunction "1_1") (pintype "passive"))
      (node (ref "Y4") (pin "8") (pinfunction "OUT_8") (pintype "passive"))
    )
    (net (code "61") (name "Net-(Y5-IN)") (class "Default")
      (node (ref "C50") (pin "2") (pinfunction "2_2") (pintype "passive"))
      (node (ref "Y5") (pin "1") (pinfunction "IN_1") (pintype "passive"))
    )
    (net (code "62") (name "Net-(Y5-OUT)") (class "Default")
      (node (ref "C63") (pin "1") (pinfunction "1_1") (pintype "passive"))
      (node (ref "Y5") (pin "2") (pinfunction "OUT_2") (pintype "passive"))
    )
    (net (code "63") (name "Net-(Y6-IN)") (class "Default")
      (node (ref "C65") (pin "2") (pinfunction "2_2") (pintype "passive"))
      (node (ref "Y6") (pin "1") (pinfunction "IN_1") (pintype "passive"))
    )
    (net (code "64") (name "Net-(Y6-OUT)") (class "Default")
      (node (ref "C66") (pin "1") (pinfunction "1_1") (pintype "passive"))
      (node (ref "Y6") (pin "2") (pinfunction "OUT_2") (pintype "passive"))
    )
    (net (code "65") (name "VCCSW") (class "Default")
      (node (ref "FB11") (pin "2") (pinfunction "2_2") (pintype "passive"))
      (node (ref "FB7") (pin "1") (pinfunction "1_1") (pintype "passive"))
      (node (ref "FB8") (pin "2") (pinfunction "2_2") (pintype "passive"))
      (node (ref "FB9") (pin "2") (pinfunction "2_2") (pintype "passive"))
    )
  )
)
